# current_sensor.net
KiCad netlist of a schematic drawn in EAGLE
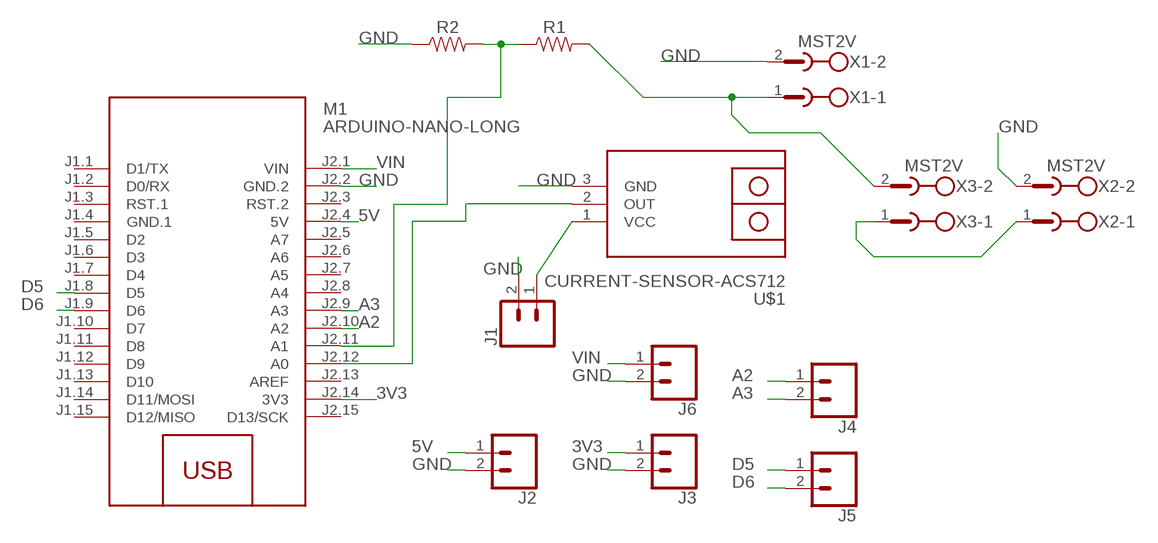
[diagram p0: schematic, sheet 1]

(export (version "E")
  (design (tool "Eeschema 10.0.6"))
  (components
    (comp (ref "J1")
      (value "CONN_02LOCK_LONGPADS")
      (footprint "eagle-import:1X02_LOCK_LONGPADS")
      (libsource (lib "eagle-import") (part "CONN_02LOCK_LONGPADS"))
    )
    (comp (ref "J2")
      (value "CONN_02LOCK_LONGPADS")
      (footprint "eagle-import:1X02_LOCK_LONGPADS")
      (libsource (lib "eagle-import") (part "CONN_02LOCK_LONGPADS"))
    )
    (comp (ref "J3")
      (value "CONN_02LOCK_LONGPADS")
      (footprint "eagle-import:1X02_LOCK_LONGPADS")
      (libsource (lib "eagle-import") (part "CONN_02LOCK_LONGPADS"))
    )
    (comp (ref "J4")
      (value "CONN_02LOCK_LONGPADS")
      (footprint "eagle-import:1X02_LOCK_LONGPADS")
      (libsource (lib "eagle-import") (part "CONN_02LOCK_LONGPADS"))
    )
    (comp (ref "J5")
      (value "CONN_02LOCK_LONGPADS")
      (footprint "eagle-import:1X02_LOCK_LONGPADS")
      (libsource (lib "eagle-import") (part "CONN_02LOCK_LONGPADS"))
    )
    (comp (ref "J6")
      (value "CONN_02LOCK_LONGPADS")
      (footprint "eagle-import:1X02_LOCK_LONGPADS")
      (libsource (lib "eagle-import") (part "CONN_02LOCK_LONGPADS"))
    )
    (comp (ref "M1")
      (value "ARDUINO-NANO-LONG")
      (footprint "eagle-import:ARDUINO-NANO-LONG")
      (libsource (lib "eagle-import") (part "ARDUINO-NANO-LONG"))
    )
    (comp (ref "R1")
      (value "RESISTORAXIAL-0.3")
      (footprint "eagle-import:AXIAL-0.3")
      (libsource (lib "eagle-import") (part "RESISTORAXIAL-0.3"))
    )
    (comp (ref "R2")
      (value "RESISTORAXIAL-0.3")
      (footprint "eagle-import:AXIAL-0.3")
      (libsource (lib "eagle-import") (part "RESISTORAXIAL-0.3"))
    )
    (comp (ref "U$1")
      (value "CURRENT-SENSOR-ACS712")
      (footprint "eagle-import:CURRENT-SENSOR-ACS712")
      (libsource (lib "eagle-import") (part "CURRENT-SENSOR-ACS712"))
    )
    (comp (ref "X1")
      (value "MST2V")
      (footprint "eagle-import:MSTBV2")
      (libsource (lib "eagle-import") (part "MST2V"))
    )
    (comp (ref "X2")
      (value "MST2V")
      (footprint "eagle-import:MSTBV2")
      (libsource (lib "eagle-import") (part "MST2V"))
    )
    (comp (ref "X3")
      (value "MST2V")
      (footprint "eagle-import:MSTBV2")
      (libsource (lib "eagle-import") (part "MST2V"))
    )
  )
  (nets
    (net (code "1") (name "/3V3") (class "Default")
      (node (ref "J3") (pin "1") (pinfunction "1_1") (pintype "passive"))
      (node (ref "M1") (pin "J2.14") (pinfunction "3V3_J2.14") (pintype "power_in"))
    )
    (net (code "2") (name "/5V") (class "Default")
      (node (ref "J2") (pin "1") (pinfunction "1_1") (pintype "passive"))
      (node (ref "M1") (pin "J2.4") (pinfunction "5V_J2.4") (pintype "power_in"))
    )
    (net (code "3") (name "/A2") (class "Default")
      (node (ref "J4") (pin "1") (pinfunction "1_1") (pintype "passive"))
      (node (ref "M1") (pin "J2.10") (pinfunction "A2_J2.10") (pintype "bidirectional"))
    )
    (net (code "4") (name "/A3") (class "Default")
      (node (ref "J4") (pin "2") (pinfunction "2_2") (pintype "passive"))
      (node (ref "M1") (pin "J2.9") (pinfunction "A3_J2.9") (pintype "bidirectional"))
    )
    (net (code "5") (name "/D5") (class "Default")
      (node (ref "J5") (pin "1") (pinfunction "1_1") (pintype "passive"))
      (node (ref "M1") (pin "J1.8") (pinfunction "D5_J1.8") (pintype "bidirectional"))
    )
    (net (code "6") (name "/D6") (class "Default")
      (node (ref "J5") (pin "2") (pinfunction "2_2") (pintype "passive"))
      (node (ref "M1") (pin "J1.9") (pinfunction "D6_J1.9") (pintype "bidirectional"))
    )
    (net (code "7") (name "/GND") (class "Default")
      (node (ref "J1") (pin "2") (pinfunction "2_2") (pintype "passive"))
      (node (ref "J2") (pin "2") (pinfunction "2_2") (pintype "passive"))
      (node (ref "J3") (pin "2") (pinfunction "2_2") (pintype "passive"))
      (node (ref "J6") (pin "2") (pinfunction "2_2") (pintype "passive"))
      (node (ref "M1") (pin "J2.2") (pinfunction "GND.2_J2.2") (pintype "power_in"))
      (node (ref "R2") (pin "P$1") (pinfunction "1_P$1") (pintype "passive"))
      (node (ref "U$1") (pin "3") (pinfunction "GND_3") (pintype "power_in"))
      (node (ref "X1") (pin "2") (pinfunction "1_2") (pintype "passive"))
      (node (ref "X2") (pin "2") (pinfunction "1_2") (pintype "passive"))
    )
    (net (code "8") (name "/GND.1") (class "Default")
      (node (ref "M1") (pin "J1.4") (pinfunction "GND.1_J1.4") (pintype "power_in"))
    )
    (net (code "9") (name "/VIN") (class "Default")
      (node (ref "J6") (pin "1") (pinfunction "1_1") (pintype "passive"))
      (node (ref "M1") (pin "J2.1") (pinfunction "VIN_J2.1") (pintype "power_in"))
    )
    (net (code "10") (name "Net-(M1-A0)") (class "Default")
      (node (ref "M1") (pin "J2.12") (pinfunction "A0_J2.12") (pintype "bidirectional"))
      (node (ref "U$1") (pin "2") (pinfunction "OUT_2") (pintype "output"))
    )
    (net (code "11") (name "Net-(M1-A1)") (class "Default")
      (node (ref "M1") (pin "J2.11") (pinfunction "A1_J2.11") (pintype "bidirectional"))
      (node (ref "R1") (pin "P$1") (pinfunction "1_P$1") (pintype "passive"))
      (node (ref "R2") (pin "P$2") (pinfunction "2_P$2") (pintype "passive"))
    )
    (net (code "12") (name "Net-(R1-2)") (class "Default")
      (node (ref "R1") (pin "P$2") (pinfunction "2_P$2") (pintype "passive"))
      (node (ref "X1") (pin "1") (pinfunction "1_1") (pintype "passive"))
      (node (ref "X3") (pin "2") (pinfunction "1_2") (pintype "passive"))
    )
    (net (code "13") (name "Net-(U$1-VCC)") (class "Default")
      (node (ref "J1") (pin "1") (pinfunction "1_1") (pintype "passive"))
      (node (ref "U$1") (pin "1") (pinfunction "VCC_1") (pintype "power_in"))
    )
    (net (code "14") (name "Net-(X2-Pad1)") (class "Default")
      (node (ref "X2") (pin "1") (pinfunction "1_1") (pintype "passive"))
      (node (ref "X3") (pin "1") (pinfunction "1_1") (pintype "passive"))
    )
    (net (code "15") (name "unconnected-(M1-A4-PadJ2.8)") (class "Default")
      (node (ref "M1") (pin "J2.8") (pinfunction "A4_J2.8") (pintype "bidirectional"))
    )
    (net (code "16") (name "unconnected-(M1-A5-PadJ2.7)") (class "Default")
      (node (ref "M1") (pin "J2.7") (pinfunction "A5_J2.7") (pintype "bidirectional"))
    )
    (net (code "17") (name "unconnected-(M1-A6-PadJ2.6)") (class "Default")
      (node (ref "M1") (pin "J2.6") (pinfunction "A6_J2.6") (pintype "bidirectional"))
    )
    (net (code "18") (name "unconnected-(M1-A7-PadJ2.5)") (class "Default")
      (node (ref "M1") (pin "J2.5") (pinfunction "A7_J2.5") (pintype "bidirectional"))
    )
    (net (code "19") (name "unconnected-(M1-AREF-PadJ2.13)") (class "Default")
      (node (ref "M1") (pin "J2.13") (pinfunction "AREF_J2.13") (pintype "bidirectional"))
    )
    (net (code "20") (name "unconnected-(M1-D0{slash}RX-PadJ1.2)") (class "Default")
      (node (ref "M1") (pin "J1.2") (pinfunction "D0/RX_J1.2") (pintype "bidirectional"))
    )
    (net (code "21") (name "unconnected-(M1-D1{slash}TX-PadJ1.1)") (class "Default")
      (node (ref "M1") (pin "J1.1") (pinfunction "D1/TX_J1.1") (pintype "bidirectional"))
    )
    (net (code "22") (name "unconnected-(M1-D2-PadJ1.5)") (class "Default")
      (node (ref "M1") (pin "J1.5") (pinfunction "D2_J1.5") (pintype "bidirectional"))
    )
    (net (code "23") (name "unconnected-(M1-D3-PadJ1.6)") (class "Default")
      (node (ref "M1") (pin "J1.6") (pinfunction "D3_J1.6") (pintype "bidirectional"))
    )
    (net (code "24") (name "unconnected-(M1-D4-PadJ1.7)") (class "Default")
      (node (ref "M1") (pin "J1.7") (pinfunction "D4_J1.7") (pintype "bidirectional"))
    )
    (net (code "25") (name "unconnected-(M1-D7-PadJ1.10)") (class "Default")
      (node (ref "M1") (pin "J1.10") (pinfunction "D7_J1.10") (pintype "bidirectional"))
    )
    (net (code "26") (name "unconnected-(M1-D8-PadJ1.11)") (class "Default")
      (node (ref "M1") (pin "J1.11") (pinfunction "D8_J1.11") (pintype "bidirectional"))
    )
    (net (code "27") (name "unconnected-(M1-D9-PadJ1.12)") (class "Default")
      (node (ref "M1") (pin "J1.12") (pinfunction "D9_J1.12") (pintype "bidirectional"))
    )
    (net (code "28") (name "unconnected-(M1-D10-PadJ1.13)") (class "Default")
      (node (ref "M1") (pin "J1.13") (pinfunction "D10_J1.13") (pintype "bidirectional"))
    )
    (net (code "29") (name "unconnected-(M1-D11{slash}MOSI-PadJ1.14)") (class "Default")
      (node (ref "M1") (pin "J1.14") (pinfunction "D11/MOSI_J1.14") (pintype "bidirectional"))
    )
    (net (code "30") (name "unconnected-(M1-D12{slash}MISO-PadJ1.15)") (class "Default")
      (node (ref "M1") (pin "J1.15") (pinfunction "D12/MISO_J1.15") (pintype "bidirectional"))
    )
    (net (code "31") (name "unconnected-(M1-D13{slash}SCK-PadJ2.15)") (class "Default")
      (node (ref "M1") (pin "J2.15") (pinfunction "D13/SCK_J2.15") (pintype "bidirectional"))
    )
    (net (code "32") (name "unconnected-(M1-RST.1-PadJ1.3)") (class "Default")
      (node (ref "M1") (pin "J1.3") (pinfunction "RST.1_J1.3") (pintype "bidirectional"))
    )
    (net (code "33") (name "unconnected-(M1-RST.2-PadJ2.3)") (class "Default")
      (node (ref "M1") (pin "J2.3") (pinfunction "RST.2_J2.3") (pintype "bidirectional"))
    )
  )
)
